# cansat.net
KiCad netlist of a schematic drawn in EAGLE
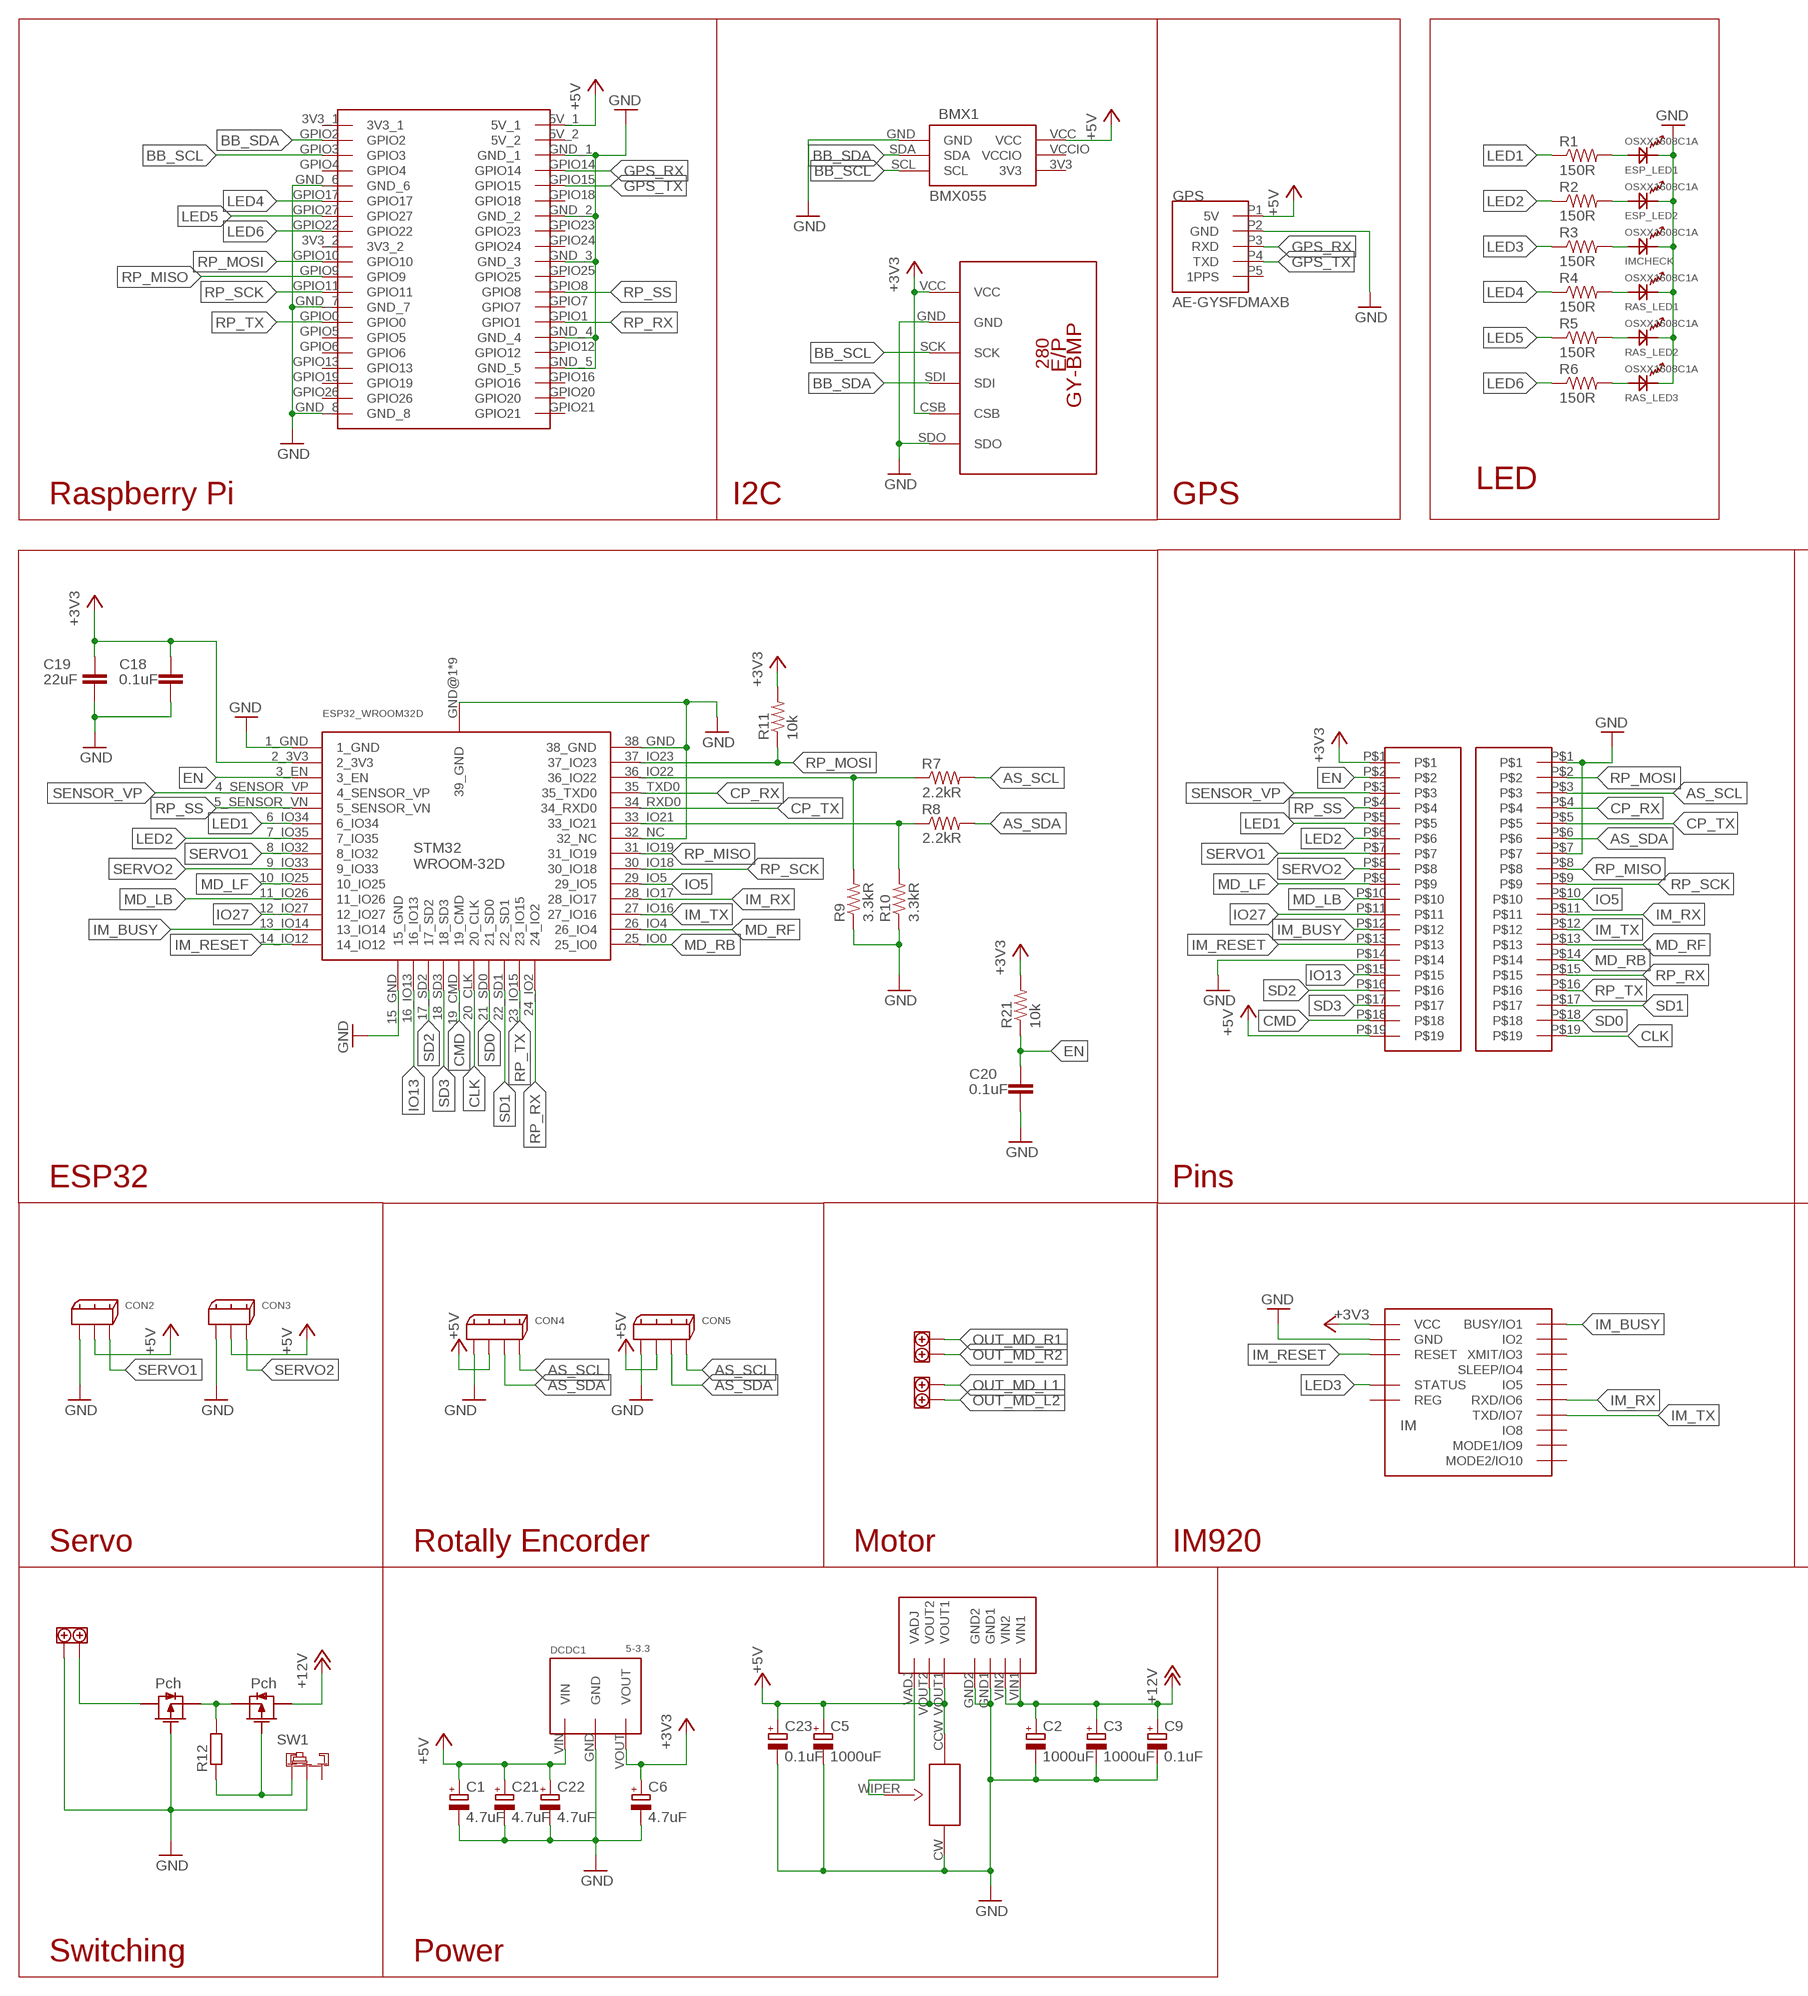
[diagram p0: schematic, sheet 1, part 1 of 2]
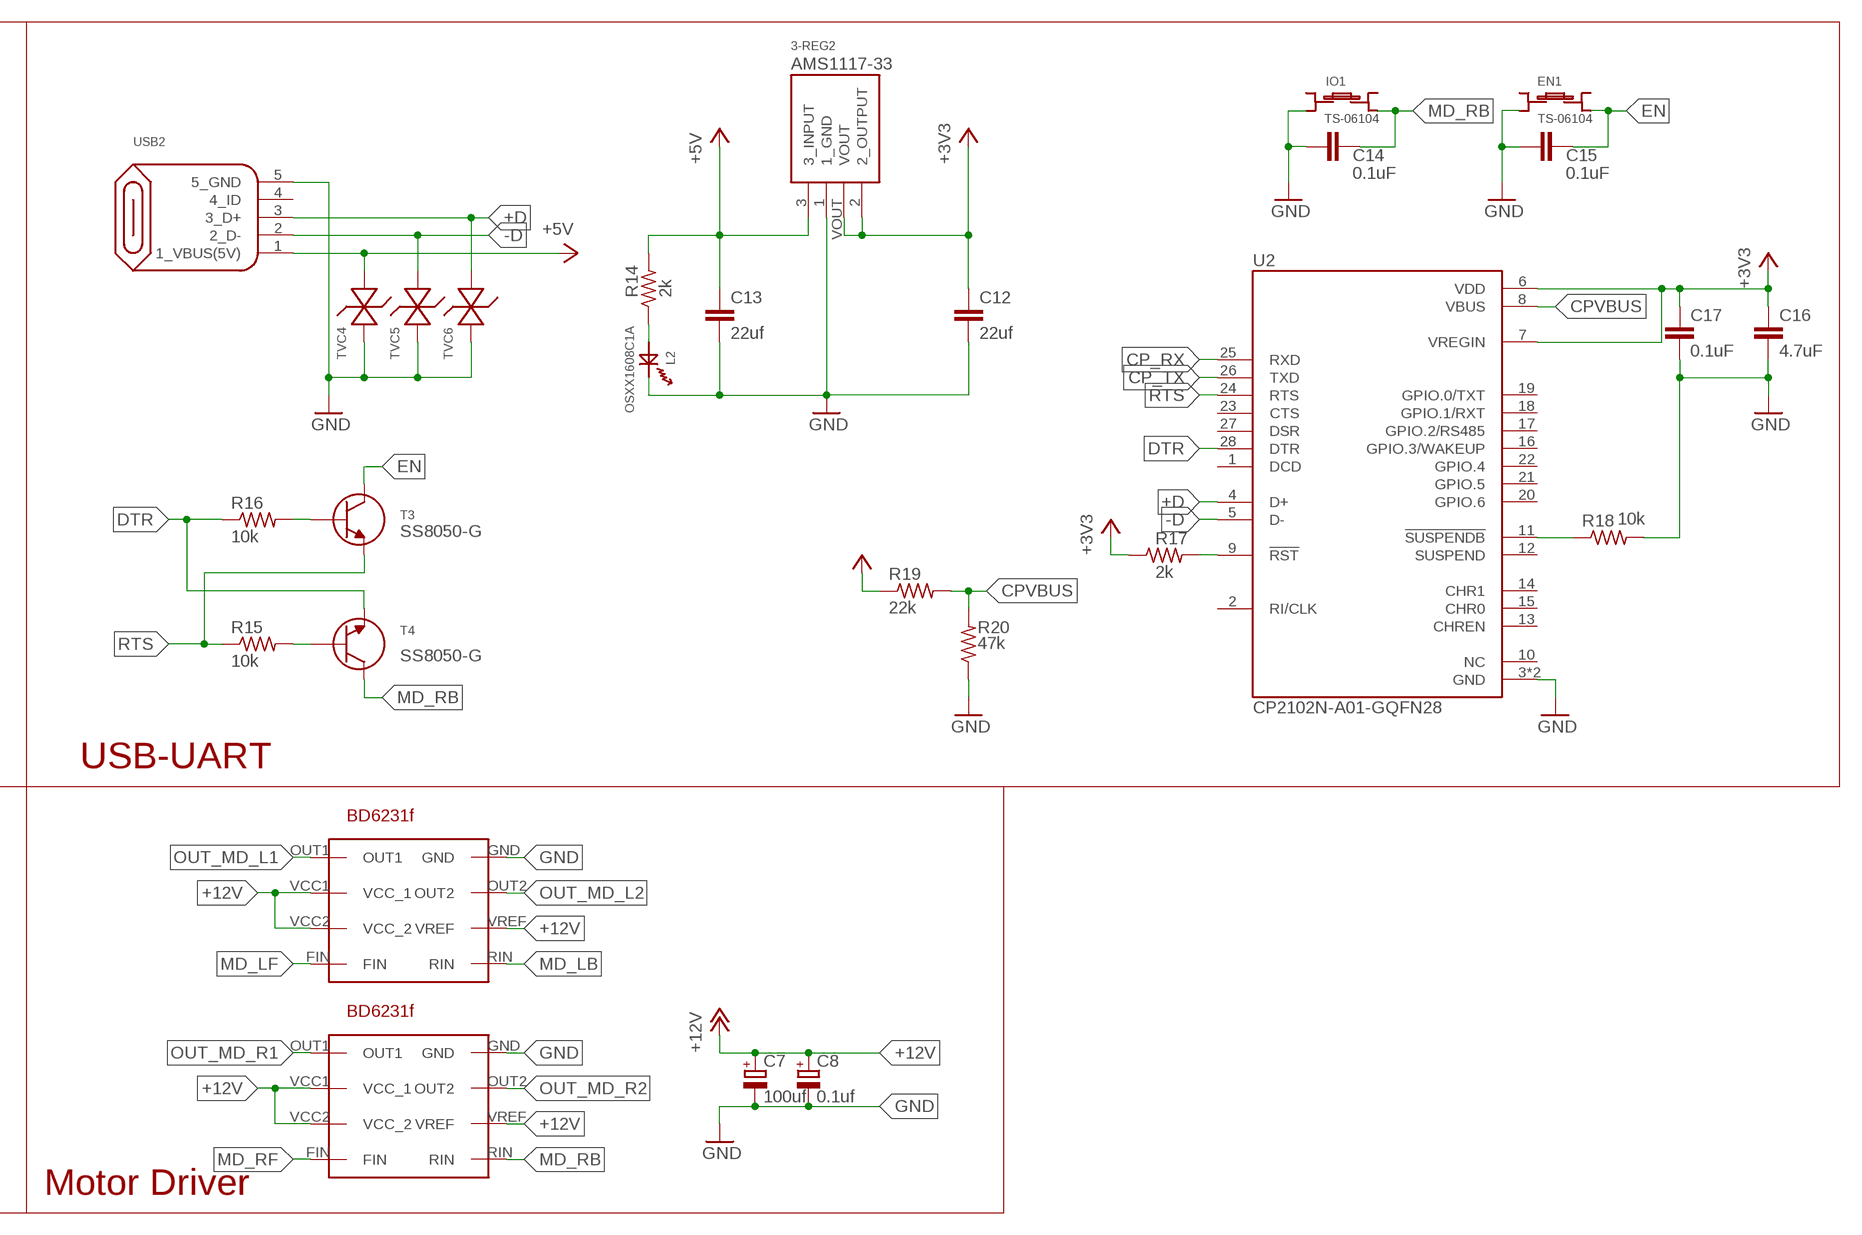
[diagram p1: schematic, sheet 1, part 2 of 2]

(export (version "E")
  (design (tool "Eeschema 10.0.6"))
  (components
    (comp (ref "3-REG2")
      (value "AZ1117CH-3.3TRG1")
      (footprint "eagle-import:AZ1117CH-3.3TRG1")
      (libsource (lib "eagle-import") (part "AZ1117CH-3.3TRG1"))
    )
    (comp (ref "100KR1")
      (value "100kR")
      (footprint "eagle-import:3362P")
      (libsource (lib "eagle-import") (part "3362P"))
    )
    (comp (ref "BMX1")
      (value "BMX055")
      (footprint "eagle-import:BMX055")
      (libsource (lib "eagle-import") (part "BMX055"))
    )
    (comp (ref "C1")
      (value "4.7uF")
      (footprint "eagle-import:E2,5-7")
      (libsource (lib "eagle-import") (part "CPOL-EUE2.5-7"))
    )
    (comp (ref "C2")
      (value "1000uF")
      (footprint "eagle-import:E5-10,5")
      (libsource (lib "eagle-import") (part "CPOL-EUE5-10.5"))
    )
    (comp (ref "C3")
      (value "1000uF")
      (footprint "eagle-import:E5-10,5")
      (libsource (lib "eagle-import") (part "CPOL-EUE5-10.5"))
    )
    (comp (ref "C5")
      (value "1000uF")
      (footprint "eagle-import:E5-10,5")
      (libsource (lib "eagle-import") (part "CPOL-EUE5-10.5"))
    )
    (comp (ref "C6")
      (value "4.7uF")
      (footprint "eagle-import:E2,5-7")
      (libsource (lib "eagle-import") (part "CPOL-EUE2.5-7"))
    )
    (comp (ref "C7")
      (value "100uf")
      (footprint "eagle-import:E2,5-7")
      (libsource (lib "eagle-import") (part "CPOL-EUE2.5-7"))
    )
    (comp (ref "C8")
      (value "0.1uf")
      (footprint "eagle-import:E2,5-7")
      (libsource (lib "eagle-import") (part "CPOL-EUE2.5-7"))
    )
    (comp (ref "C9")
      (value "0.1uF")
      (footprint "eagle-import:E2,5-7")
      (libsource (lib "eagle-import") (part "CPOL-EUE2.5-7"))
    )
    (comp (ref "C12")
      (value "22uf")
      (footprint "eagle-import:C0603")
      (libsource (lib "eagle-import") (part "C-EUC0603"))
    )
    (comp (ref "C13")
      (value "22uf")
      (footprint "eagle-import:C0603")
      (libsource (lib "eagle-import") (part "C-EUC0603"))
    )
    (comp (ref "C14")
      (value "0.1uF")
      (footprint "eagle-import:C0603")
      (libsource (lib "eagle-import") (part "C-EUC0603"))
    )
    (comp (ref "C15")
      (value "0.1uF")
      (footprint "eagle-import:C0603")
      (libsource (lib "eagle-import") (part "C-EUC0603"))
    )
    (comp (ref "C16")
      (value "4.7uF")
      (footprint "eagle-import:C0402")
      (libsource (lib "eagle-import") (part "C-EUC0402"))
    )
    (comp (ref "C17")
      (value "0.1uF")
      (footprint "eagle-import:C0603")
      (libsource (lib "eagle-import") (part "C-EUC0603"))
    )
    (comp (ref "C18")
      (value "0.1uF")
      (footprint "eagle-import:C0603")
      (libsource (lib "eagle-import") (part "C-EUC0603"))
    )
    (comp (ref "C19")
      (value "22uF")
      (footprint "eagle-import:C0603")
      (libsource (lib "eagle-import") (part "C-EUC0603"))
    )
    (comp (ref "C20")
      (value "0.1uF")
      (footprint "eagle-import:C0603")
      (libsource (lib "eagle-import") (part "C-EUC0603"))
    )
    (comp (ref "C21")
      (value "4.7uF")
      (footprint "eagle-import:E2,5-7")
      (libsource (lib "eagle-import") (part "CPOL-EUE2.5-7"))
    )
    (comp (ref "C22")
      (value "4.7uF")
      (footprint "eagle-import:E2,5-7")
      (libsource (lib "eagle-import") (part "CPOL-EUE2.5-7"))
    )
    (comp (ref "C23")
      (value "0.1uF")
      (footprint "eagle-import:E5-10,5")
      (libsource (lib "eagle-import") (part "CPOL-EUE5-10.5"))
    )
    (comp (ref "CON2")
      (value "2.5_MINI-SPOX_3PIN")
      (footprint "eagle-import:2.5_MINI-SPOX_3PIN")
      (libsource (lib "eagle-import") (part "2.5_MINI-SPOX_3PIN"))
    )
    (comp (ref "CON3")
      (value "2.5_MINI-SPOX_3PIN")
      (footprint "eagle-import:2.5_MINI-SPOX_3PIN")
      (libsource (lib "eagle-import") (part "2.5_MINI-SPOX_3PIN"))
    )
    (comp (ref "CON4")
      (value "2.5_MINI-SPOX_4PIN")
      (footprint "eagle-import:2.5_MINI-SPOX_4PIN")
      (libsource (lib "eagle-import") (part "2.5_MINI-SPOX_4PIN"))
    )
    (comp (ref "CON5")
      (value "2.5_MINI-SPOX_4PIN")
      (footprint "eagle-import:2.5_MINI-SPOX_4PIN")
      (libsource (lib "eagle-import") (part "2.5_MINI-SPOX_4PIN"))
    )
    (comp (ref "DCDC1")
      (value "5-3.3")
      (footprint "eagle-import:3.3V0.5A_M78AR05-0.5")
      (libsource (lib "eagle-import") (part "3.3V0.5A_M78AR05-0.5"))
    )
    (comp (ref "EN1")
      (value "TS-06104")
      (footprint "eagle-import:TS-06104")
      (libsource (lib "eagle-import") (part "TS-06104"))
    )
    (comp (ref "ESP32_WROOM32D")
      (value "ESP32-WROOM-32D")
      (footprint "eagle-import:ESP32-WROOM-32D")
      (libsource (lib "eagle-import") (part "ESP32-WROOM-32D"))
    )
    (comp (ref "ESP_LED1")
      (value "OSXX1608C1A")
      (footprint "eagle-import:OSXX1608C1A")
      (libsource (lib "eagle-import") (part "OSXX1608C1A"))
    )
    (comp (ref "ESP_LED2")
      (value "OSXX1608C1A")
      (footprint "eagle-import:OSXX1608C1A")
      (libsource (lib "eagle-import") (part "OSXX1608C1A"))
    )
    (comp (ref "GPS")
      (value "AE-GYSFDMAXB")
      (footprint "eagle-import:AE-GYSFDMAXB")
      (libsource (lib "eagle-import") (part "AE-GYSFDMAXB"))
    )
    (comp (ref "IM")
      (value "IM920C")
      (footprint "eagle-import:IM920C")
      (libsource (lib "eagle-import") (part "IM920C"))
    )
    (comp (ref "IMCHECK")
      (value "OSXX1608C1A")
      (footprint "eagle-import:OSXX1608C1A")
      (libsource (lib "eagle-import") (part "OSXX1608C1A"))
    )
    (comp (ref "IO1")
      (value "TS-06104")
      (footprint "eagle-import:TS-06104")
      (libsource (lib "eagle-import") (part "TS-06104"))
    )
    (comp (ref "L2")
      (value "OSXX1608C1A")
      (footprint "eagle-import:OSXX1608C1A")
      (libsource (lib "eagle-import") (part "OSXX1608C1A"))
    )
    (comp (ref "MD_L")
      (value "BD6231F")
      (footprint "eagle-import:BD6231F")
      (libsource (lib "eagle-import") (part "BD6231F"))
    )
    (comp (ref "MD_R")
      (value "BD6231F")
      (footprint "eagle-import:BD6231F")
      (libsource (lib "eagle-import") (part "BD6231F"))
    )
    (comp (ref "PIN_L")
      (value "19_2.54")
      (footprint "eagle-import:19_2.54")
      (libsource (lib "eagle-import") (part "19_2.54"))
    )
    (comp (ref "PIN_R")
      (value "19_2.54")
      (footprint "eagle-import:19_2.54")
      (libsource (lib "eagle-import") (part "19_2.54"))
    )
    (comp (ref "R1")
      (value "150R")
      (footprint "eagle-import:R0603")
      (libsource (lib "eagle-import") (part "R-US_R0603"))
    )
    (comp (ref "R2")
      (value "150R")
      (footprint "eagle-import:R0603")
      (libsource (lib "eagle-import") (part "R-US_R0603"))
    )
    (comp (ref "R3")
      (value "150R")
      (footprint "eagle-import:R0603")
      (libsource (lib "eagle-import") (part "R-US_R0603"))
    )
    (comp (ref "R4")
      (value "150R")
      (footprint "eagle-import:R0603")
      (libsource (lib "eagle-import") (part "R-US_R0603"))
    )
    (comp (ref "R5")
      (value "150R")
      (footprint "eagle-import:R0603")
      (libsource (lib "eagle-import") (part "R-US_R0603"))
    )
    (comp (ref "R6")
      (value "150R")
      (footprint "eagle-import:R0603")
      (libsource (lib "eagle-import") (part "R-US_R0603"))
    )
    (comp (ref "R7")
      (value "2.2kR")
      (footprint "eagle-import:R0603")
      (libsource (lib "eagle-import") (part "R-US_R0603"))
    )
    (comp (ref "R8")
      (value "2.2kR")
      (footprint "eagle-import:R0603")
      (libsource (lib "eagle-import") (part "R-US_R0603"))
    )
    (comp (ref "R9")
      (value "3.3kR")
      (footprint "eagle-import:R0603")
      (libsource (lib "eagle-import") (part "R-US_R0603"))
    )
    (comp (ref "R10")
      (value "3.3kR")
      (footprint "eagle-import:R0603")
      (libsource (lib "eagle-import") (part "R-US_R0603"))
    )
    (comp (ref "R11")
      (value "10k")
      (footprint "eagle-import:R0201")
      (libsource (lib "eagle-import") (part "R-US_R0201"))
    )
    (comp (ref "R12")
      (value "R-EU_0207/10")
      (footprint "eagle-import:0207_10")
      (libsource (lib "eagle-import") (part "R-EU_0207/10"))
    )
    (comp (ref "R14")
      (value "2k")
      (footprint "eagle-import:R0201")
      (libsource (lib "eagle-import") (part "R-US_R0201"))
    )
    (comp (ref "R15")
      (value "10k")
      (footprint "eagle-import:R0201")
      (libsource (lib "eagle-import") (part "R-US_R0201"))
    )
    (comp (ref "R16")
      (value "10k")
      (footprint "eagle-import:R0201")
      (libsource (lib "eagle-import") (part "R-US_R0201"))
    )
    (comp (ref "R17")
      (value "2k")
      (footprint "eagle-import:R0201")
      (libsource (lib "eagle-import") (part "R-US_R0201"))
    )
    (comp (ref "R18")
      (value "10k")
      (footprint "eagle-import:R0201")
      (libsource (lib "eagle-import") (part "R-US_R0201"))
    )
    (comp (ref "R19")
      (value "22k")
      (footprint "eagle-import:R0201")
      (libsource (lib "eagle-import") (part "R-US_R0201"))
    )
    (comp (ref "R20")
      (value "47k")
      (footprint "eagle-import:R0201")
      (libsource (lib "eagle-import") (part "R-US_R0201"))
    )
    (comp (ref "R21")
      (value "10k")
      (footprint "eagle-import:R0201")
      (libsource (lib "eagle-import") (part "R-US_R0201"))
    )
    (comp (ref "RASPBERRYPI_4B")
      (value "RASPBERRYPI4B")
      (footprint "eagle-import:RASPBERRYPI4B")
      (libsource (lib "eagle-import") (part "RASPBERRYPI4B"))
    )
    (comp (ref "RAS_LED1")
      (value "OSXX1608C1A")
      (footprint "eagle-import:OSXX1608C1A")
      (libsource (lib "eagle-import") (part "OSXX1608C1A"))
    )
    (comp (ref "RAS_LED2")
      (value "OSXX1608C1A")
      (footprint "eagle-import:OSXX1608C1A")
      (libsource (lib "eagle-import") (part "OSXX1608C1A"))
    )
    (comp (ref "RAS_LED3")
      (value "OSXX1608C1A")
      (footprint "eagle-import:OSXX1608C1A")
      (libsource (lib "eagle-import") (part "OSXX1608C1A"))
    )
    (comp (ref "SW1")
      (value "SRIDE_SWITCH")
      (footprint "eagle-import:SRIDE_SWITCH")
      (libsource (lib "eagle-import") (part "SRIDE_SWITCH"))
    )
    (comp (ref "T3")
      (value "NPN_SS8050-G")
      (footprint "eagle-import:NPN_SS8050-G")
      (libsource (lib "eagle-import") (part "NPN_SS8050-G"))
    )
    (comp (ref "T4")
      (value "NPN_SS8050-G")
      (footprint "eagle-import:NPN_SS8050-G")
      (libsource (lib "eagle-import") (part "NPN_SS8050-G"))
    )
    (comp (ref "TM1")
      (value "TERMINAL_SLOPED_2PIN")
      (footprint "eagle-import:TERMINAL_SLOPED_2PIN")
      (libsource (lib "eagle-import") (part "TERMINAL_SLOPED_2PIN"))
    )
    (comp (ref "TM2")
      (value "TERMINAL_SLOPED_2PIN")
      (footprint "eagle-import:TERMINAL_SLOPED_2PIN")
      (libsource (lib "eagle-import") (part "TERMINAL_SLOPED_2PIN"))
    )
    (comp (ref "TM3")
      (value "TERMINAL_SLOPED_2PIN")
      (footprint "eagle-import:TERMINAL_SLOPED_2PIN")
      (libsource (lib "eagle-import") (part "TERMINAL_SLOPED_2PIN"))
    )
    (comp (ref "TVC4")
      (value "ESD5484FCT5G")
      (footprint "eagle-import:ESD5484FCT5G")
      (libsource (lib "eagle-import") (part "ESD5484FCT5G"))
    )
    (comp (ref "TVC5")
      (value "ESD5484FCT5G")
      (footprint "eagle-import:ESD5484FCT5G")
      (libsource (lib "eagle-import") (part "ESD5484FCT5G"))
    )
    (comp (ref "TVC6")
      (value "ESD5484FCT5G")
      (footprint "eagle-import:ESD5484FCT5G")
      (libsource (lib "eagle-import") (part "ESD5484FCT5G"))
    )
    (comp (ref "U$7")
      (value "2SJ681-PCH")
      (footprint "eagle-import:2SJ681")
      (libsource (lib "eagle-import") (part "2SJ681-PCH"))
    )
    (comp (ref "U$8")
      (value "5V3A_KIC-053")
      (footprint "eagle-import:5V3A_KIC-053")
      (libsource (lib "eagle-import") (part "5V3A_KIC-053"))
    )
    (comp (ref "U$9")
      (value "GY-BPM280")
      (footprint "eagle-import:GY-BMP280-FOOTPRINT")
      (libsource (lib "eagle-import") (part "GY-BPM280"))
    )
    (comp (ref "U$10")
      (value "2SJ681-PCH")
      (footprint "eagle-import:2SJ681")
      (libsource (lib "eagle-import") (part "2SJ681-PCH"))
    )
    (comp (ref "U2")
      (value "CP2102N-A01-GQFN28")
      (footprint "eagle-import:QFN50P500X500X80-29N")
      (fields (field (name "MF") "Silicon Labs"))
      (libsource (lib "eagle-import") (part "CP2102N-A01-GQFN28"))
    )
    (comp (ref "USB2")
      (value "MICRO-B_ZX62R-B-5P")
      (footprint "eagle-import:MICRO-B_ZX62R-B-5P")
      (libsource (lib "eagle-import") (part "MICRO-B_ZX62R-B-5P"))
    )
  )
  (nets
    (net (code "1") (name "+3V3") (class "Default")
      (node (ref "3-REG2") (pin "2") (pinfunction "2_OUTPUT_2") (pintype "bidirectional"))
      (node (ref "3-REG2") (pin "VOUT") (pinfunction "VOUT_VOUT") (pintype "bidirectional"))
      (node (ref "C12") (pin "1") (pinfunction "1_1") (pintype "passive"))
      (node (ref "C16") (pin "1") (pinfunction "1_1") (pintype "passive"))
      (node (ref "C17") (pin "1") (pinfunction "1_1") (pintype "passive"))
      (node (ref "C18") (pin "1") (pinfunction "1_1") (pintype "passive"))
      (node (ref "C19") (pin "1") (pinfunction "1_1") (pintype "passive"))
      (node (ref "C6") (pin "+") (pinfunction "+_+") (pintype "passive"))
      (node (ref "DCDC1") (pin "VOUT") (pinfunction "VOUT_VOUT") (pintype "bidirectional"))
      (node (ref "ESP32_WROOM32D") (pin "2_3V3") (pinfunction "2_3V3_2_3V3") (pintype "bidirectional"))
      (node (ref "IM") (pin "$P17") (pinfunction "VCC_$P17") (pintype "bidirectional"))
      (node (ref "PIN_L") (pin "P$1") (pinfunction "P$1_P$1") (pintype "bidirectional"))
      (node (ref "R11") (pin "2") (pinfunction "2_2") (pintype "passive"))
      (node (ref "R17") (pin "1") (pinfunction "1_1") (pintype "passive"))
      (node (ref "R21") (pin "2") (pinfunction "2_2") (pintype "passive"))
      (node (ref "U$9") (pin "CSB") (pinfunction "CSB_CSB") (pintype "bidirectional"))
      (node (ref "U$9") (pin "VCC") (pinfunction "VCC_VCC") (pintype "bidirectional"))
      (node (ref "U2") (pin "6") (pinfunction "VDD_6") (pintype "power_in"))
      (node (ref "U2") (pin "7") (pinfunction "VREGIN_7") (pintype "power_in"))
    )
    (net (code "2") (name "+5V") (class "Default")
      (node (ref "100KR1") (pin "CCW") (pinfunction "CCW_CCW") (pintype "bidirectional"))
      (node (ref "3-REG2") (pin "3") (pinfunction "3_INPUT_3") (pintype "bidirectional"))
      (node (ref "BMX1") (pin "VCC") (pinfunction "VCC_VCC") (pintype "power_in"))
      (node (ref "C1") (pin "+") (pinfunction "+_+") (pintype "passive"))
      (node (ref "C13") (pin "1") (pinfunction "1_1") (pintype "passive"))
      (node (ref "C21") (pin "+") (pinfunction "+_+") (pintype "passive"))
      (node (ref "C22") (pin "+") (pinfunction "+_+") (pintype "passive"))
      (node (ref "C23") (pin "+") (pinfunction "+_+") (pintype "passive"))
      (node (ref "C5") (pin "+") (pinfunction "+_+") (pintype "passive"))
      (node (ref "CON2") (pin "2") (pinfunction "2_2") (pintype "bidirectional"))
      (node (ref "CON3") (pin "2") (pinfunction "2_2") (pintype "bidirectional"))
      (node (ref "CON4") (pin "P$2") (pinfunction "2_P$2") (pintype "bidirectional"))
      (node (ref "CON5") (pin "P$2") (pinfunction "2_P$2") (pintype "bidirectional"))
      (node (ref "DCDC1") (pin "VIN") (pinfunction "VIN_VIN") (pintype "bidirectional"))
      (node (ref "GPS") (pin "P1") (pinfunction "5V_P1") (pintype "bidirectional"))
      (node (ref "PIN_L") (pin "P$19") (pinfunction "P$19_P$19") (pintype "bidirectional"))
      (node (ref "R14") (pin "2") (pinfunction "2_2") (pintype "passive"))
      (node (ref "R19") (pin "1") (pinfunction "1_1") (pintype "passive"))
      (node (ref "RASPBERRYPI_4B") (pin "5V_1") (pinfunction "5V_1_5V_1") (pintype "bidirectional"))
      (node (ref "TVC4") (pin "2_AN") (pinfunction "2_AN_2_AN") (pintype "bidirectional"))
      (node (ref "U$8") (pin "VOUT1") (pinfunction "VOUT1_VOUT1") (pintype "bidirectional"))
      (node (ref "U$8") (pin "VOUT2") (pinfunction "VOUT2_VOUT2") (pintype "bidirectional"))
      (node (ref "USB2") (pin "1") (pinfunction "1_VBUS(5V)_1") (pintype "bidirectional"))
    )
    (net (code "3") (name "+12V") (class "Default")
      (node (ref "C2") (pin "+") (pinfunction "+_+") (pintype "passive"))
      (node (ref "C3") (pin "+") (pinfunction "+_+") (pintype "passive"))
      (node (ref "C7") (pin "+") (pinfunction "+_+") (pintype "passive"))
      (node (ref "C8") (pin "+") (pinfunction "+_+") (pintype "passive"))
      (node (ref "C9") (pin "+") (pinfunction "+_+") (pintype "passive"))
      (node (ref "MD_L") (pin "VCC1") (pinfunction "VCC_1_VCC1") (pintype "bidirectional"))
      (node (ref "MD_L") (pin "VCC2") (pinfunction "VCC_2_VCC2") (pintype "bidirectional"))
      (node (ref "MD_L") (pin "VREF") (pinfunction "VREF_VREF") (pintype "bidirectional"))
      (node (ref "MD_R") (pin "VCC1") (pinfunction "VCC_1_VCC1") (pintype "bidirectional"))
      (node (ref "MD_R") (pin "VCC2") (pinfunction "VCC_2_VCC2") (pintype "bidirectional"))
      (node (ref "MD_R") (pin "VREF") (pinfunction "VREF_VREF") (pintype "bidirectional"))
      (node (ref "U$10") (pin "DRAIN") (pinfunction "DRAIN_DRAIN") (pintype "bidirectional"))
      (node (ref "U$8") (pin "VIN1") (pinfunction "VIN1_VIN1") (pintype "bidirectional"))
      (node (ref "U$8") (pin "VIN2") (pinfunction "VIN2_VIN2") (pintype "bidirectional"))
    )
    (net (code "4") (name "+D") (class "Default")
      (node (ref "TVC6") (pin "2_AN") (pinfunction "2_AN_2_AN") (pintype "bidirectional"))
      (node (ref "U2") (pin "4") (pinfunction "D+_4") (pintype "bidirectional"))
      (node (ref "USB2") (pin "3") (pinfunction "3_D+_3") (pintype "bidirectional"))
    )
    (net (code "5") (name "-D") (class "Default")
      (node (ref "TVC5") (pin "2_AN") (pinfunction "2_AN_2_AN") (pintype "bidirectional"))
      (node (ref "U2") (pin "5") (pinfunction "D-_5") (pintype "bidirectional"))
      (node (ref "USB2") (pin "2") (pinfunction "2_D-_2") (pintype "bidirectional"))
    )
    (net (code "6") (name "/3V3") (class "Default")
      (node (ref "BMX1") (pin "3V3") (pinfunction "3V3_3V3") (pintype "power_in"))
    )
    (net (code "7") (name "/VCCIO") (class "Default")
      (node (ref "BMX1") (pin "VCCIO") (pinfunction "VCCIO_VCCIO") (pintype "power_in"))
    )
    (net (code "8") (name "AS_SCL") (class "Default")
      (node (ref "CON4") (pin "P$4") (pinfunction "4_P$4") (pintype "bidirectional"))
      (node (ref "CON5") (pin "P$4") (pinfunction "4_P$4") (pintype "bidirectional"))
      (node (ref "PIN_R") (pin "P$3") (pinfunction "P$3_P$3") (pintype "bidirectional"))
      (node (ref "R7") (pin "2") (pinfunction "2_2") (pintype "passive"))
    )
    (net (code "9") (name "AS_SDA") (class "Default")
      (node (ref "CON4") (pin "P$3") (pinfunction "3_P$3") (pintype "bidirectional"))
      (node (ref "CON5") (pin "P$3") (pinfunction "3_P$3") (pintype "bidirectional"))
      (node (ref "PIN_R") (pin "P$6") (pinfunction "P$6_P$6") (pintype "bidirectional"))
      (node (ref "R8") (pin "2") (pinfunction "2_2") (pintype "passive"))
    )
    (net (code "10") (name "BB_SCL") (class "Default")
      (node (ref "BMX1") (pin "SCL") (pinfunction "SCL_SCL") (pintype "bidirectional"))
      (node (ref "RASPBERRYPI_4B") (pin "GPIO3") (pinfunction "GPIO3_GPIO3") (pintype "bidirectional"))
      (node (ref "U$9") (pin "SCK") (pinfunction "SCK_SCK") (pintype "bidirectional"))
    )
    (net (code "11") (name "BB_SDA") (class "Default")
      (node (ref "BMX1") (pin "SDA") (pinfunction "SDA_SDA") (pintype "bidirectional"))
      (node (ref "RASPBERRYPI_4B") (pin "GPIO2") (pinfunction "GPIO2_GPIO2") (pintype "bidirectional"))
      (node (ref "U$9") (pin "SDI") (pinfunction "SDI_SDI") (pintype "bidirectional"))
    )
    (net (code "12") (name "CLK") (class "Default")
      (node (ref "ESP32_WROOM32D") (pin "20_CLK") (pinfunction "20_CLK_20_CLK") (pintype "bidirectional"))
      (node (ref "PIN_R") (pin "P$19") (pinfunction "P$19_P$19") (pintype "bidirectional"))
    )
    (net (code "13") (name "CMD") (class "Default")
      (node (ref "ESP32_WROOM32D") (pin "19_CMD") (pinfunction "19_CMD_19_CMD") (pintype "bidirectional"))
      (node (ref "PIN_L") (pin "P$18") (pinfunction "P$18_P$18") (pintype "bidirectional"))
    )
    (net (code "14") (name "CPVBUS") (class "Default")
      (node (ref "R19") (pin "2") (pinfunction "2_2") (pintype "passive"))
      (node (ref "R20") (pin "2") (pinfunction "2_2") (pintype "passive"))
      (node (ref "U2") (pin "8") (pinfunction "VBUS_8") (pintype "power_in"))
    )
    (net (code "15") (name "CP_RX") (class "Default")
      (node (ref "ESP32_WROOM32D") (pin "35_TXD0") (pinfunction "35_TXD0_35_TXD0") (pintype "bidirectional"))
      (node (ref "PIN_R") (pin "P$4") (pinfunction "P$4_P$4") (pintype "bidirectional"))
      (node (ref "U2") (pin "25") (pinfunction "RXD_25") (pintype "input"))
    )
    (net (code "16") (name "CP_TX") (class "Default")
      (node (ref "ESP32_WROOM32D") (pin "34_RXD0") (pinfunction "34_RXD0_34_RXD0") (pintype "bidirectional"))
      (node (ref "PIN_R") (pin "P$5") (pinfunction "P$5_P$5") (pintype "bidirectional"))
      (node (ref "U2") (pin "26") (pinfunction "TXD_26") (pintype "output"))
    )
    (net (code "17") (name "DTR") (class "Default")
      (node (ref "R16") (pin "1") (pinfunction "1_1") (pintype "passive"))
      (node (ref "T4") (pin "2") (pinfunction "2_2") (pintype "bidirectional"))
      (node (ref "U2") (pin "28") (pinfunction "DTR_28") (pintype "output"))
    )
    (net (code "18") (name "EN") (class "Default")
      (node (ref "C15") (pin "1") (pinfunction "1_1") (pintype "passive"))
      (node (ref "C20") (pin "1") (pinfunction "1_1") (pintype "passive"))
      (node (ref "EN1") (pin "D") (pinfunction "D_D") (pintype "bidirectional"))
      (node (ref "ESP32_WROOM32D") (pin "3_EN") (pinfunction "3_EN_3_EN") (pintype "bidirectional"))
      (node (ref "PIN_L") (pin "P$2") (pinfunction "P$2_P$2") (pintype "bidirectional"))
      (node (ref "R21") (pin "1") (pinfunction "1_1") (pintype "passive"))
      (node (ref "T3") (pin "3") (pinfunction "3_3") (pintype "bidirectional"))
    )
    (net (code "19") (name "GND") (class "Default")
      (node (ref "100KR1") (pin "CW") (pinfunction "CW_CW") (pintype "bidirectional"))
      (node (ref "3-REG2") (pin "1") (pinfunction "1_GND_1") (pintype "bidirectional"))
      (node (ref "BMX1") (pin "GND") (pinfunction "GND_GND") (pintype "power_in"))
      (node (ref "C1") (pin "-") (pinfunction "-_-") (pintype "passive"))
      (node (ref "C12") (pin "2") (pinfunction "2_2") (pintype "passive"))
      (node (ref "C13") (pin "2") (pinfunction "2_2") (pintype "passive"))
      (node (ref "C14") (pin "2") (pinfunction "2_2") (pintype "passive"))
      (node (ref "C15") (pin "2") (pinfunction "2_2") (pintype "passive"))
      (node (ref "C16") (pin "2") (pinfunction "2_2") (pintype "passive"))
      (node (ref "C17") (pin "2") (pinfunction "2_2") (pintype "passive"))
      (node (ref "C18") (pin "2") (pinfunction "2_2") (pintype "passive"))
      (node (ref "C19") (pin "2") (pinfunction "2_2") (pintype "passive"))
      (node (ref "C2") (pin "-") (pinfunction "-_-") (pintype "passive"))
      (node (ref "C20") (pin "2") (pinfunction "2_2") (pintype "passive"))
      (node (ref "C21") (pin "-") (pinfunction "-_-") (pintype "passive"))
      (node (ref "C22") (pin "-") (pinfunction "-_-") (pintype "passive"))
      (node (ref "C23") (pin "-") (pinfunction "-_-") (pintype "passive"))
      (node (ref "C3") (pin "-") (pinfunction "-_-") (pintype "passive"))
      (node (ref "C5") (pin "-") (pinfunction "-_-") (pintype "passive"))
      (node (ref "C6") (pin "-") (pinfunction "-_-") (pintype "passive"))
      (node (ref "C7") (pin "-") (pinfunction "-_-") (pintype "passive"))
      (node (ref "C8") (pin "-") (pinfunction "-_-") (pintype "passive"))
      (node (ref "C9") (pin "-") (pinfunction "-_-") (pintype "passive"))
      (node (ref "CON2") (pin "1") (pinfunction "1_1") (pintype "bidirectional"))
      (node (ref "CON3") (pin "1") (pinfunction "1_1") (pintype "bidirectional"))
      (node (ref "CON4") (pin "P$1") (pinfunction "1_P$1") (pintype "bidirectional"))
      (node (ref "CON5") (pin "P$1") (pinfunction "1_P$1") (pintype "bidirectional"))
      (node (ref "DCDC1") (pin "GND") (pinfunction "GND_GND") (pintype "bidirectional"))
      (node (ref "EN1") (pin "B") (pinfunction "B_B") (pintype "bidirectional"))
      (node (ref "ESP32_WROOM32D") (pin "15_GND") (pinfunction "15_GND_15_GND") (pintype "bidirectional"))
      (node (ref "ESP32_WROOM32D") (pin "1_GND") (pinfunction "1_GND_1_GND") (pintype "bidirectional"))
      (node (ref "ESP32_WROOM32D") (pin "32_NC") (pinfunction "32_NC_32_NC") (pintype "bidirectional"))
      (node (ref "ESP32_WROOM32D") (pin "38_GND") (pinfunction "38_GND_38_GND") (pintype "bidirectional"))
      (node (ref "ESP32_WROOM32D") (pin "GND@1") (pinfunction "39_GND_GND@1") (pintype "bidirectional"))
      (node (ref "ESP32_WROOM32D") (pin "GND@2") (pinfunction "39_GND_GND@2") (pintype "bidirectional"))
      (node (ref "ESP32_WROOM32D") (pin "GND@3") (pinfunction "39_GND_GND@3") (pintype "bidirectional"))
      (node (ref "ESP32_WROOM32D") (pin "GND@4") (pinfunction "39_GND_GND@4") (pintype "bidirectional"))
      (node (ref "ESP32_WROOM32D") (pin "GND@5") (pinfunction "39_GND_GND@5") (pintype "bidirectional"))
      (node (ref "ESP32_WROOM32D") (pin "GND@6") (pinfunction "39_GND_GND@6") (pintype "bidirectional"))
      (node (ref "ESP32_WROOM32D") (pin "GND@7") (pinfunction "39_GND_GND@7") (pintype "bidirectional"))
      (node (ref "ESP32_WROOM32D") (pin "GND@8") (pinfunction "39_GND_GND@8") (pintype "bidirectional"))
      (node (ref "ESP32_WROOM32D") (pin "GND@9") (pinfunction "39_GND_GND@9") (pintype "bidirectional"))
      (node (ref "ESP_LED1") (pin "CT") (pinfunction "CT_CT") (pintype "bidirectional"))
      (node (ref "ESP_LED2") (pin "CT") (pinfunction "CT_CT") (pintype "bidirectional"))
      (node (ref "GPS") (pin "P2") (pinfunction "GND_P2") (pintype "bidirectional"))
      (node (ref "IM") (pin "$P18") (pinfunction "GND_$P18") (pintype "bidirectional"))
      (node (ref "IMCHECK") (pin "CT") (pinfunction "CT_CT") (pintype "bidirectional"))
      (node (ref "IO1") (pin "B") (pinfunction "B_B") (pintype "bidirectional"))
      (node (ref "L2") (pin "CT") (pinfunction "CT_CT") (pintype "bidirectional"))
      (node (ref "MD_L") (pin "GND") (pinfunction "GND_GND") (pintype "bidirectional"))
      (node (ref "MD_R") (pin "GND") (pinfunction "GND_GND") (pintype "bidirectional"))
      (node (ref "PIN_L") (pin "P$14") (pinfunction "P$14_P$14") (pintype "bidirectional"))
      (node (ref "PIN_R") (pin "P$1") (pinfunction "P$1_P$1") (pintype "bidirectional"))
      (node (ref "PIN_R") (pin "P$7") (pinfunction "P$7_P$7") (pintype "bidirectional"))
      (node (ref "R10") (pin "1") (pinfunction "1_1") (pintype "passive"))
      (node (ref "R18") (pin "2") (pinfunction "2_2") (pintype "passive"))
      (node (ref "R20") (pin "1") (pinfunction "1_1") (pintype "passive"))
      (node (ref "R9") (pin "1") (pinfunction "1_1") (pintype "passive"))
      (node (ref "RASPBERRYPI_4B") (pin "GND_1") (pinfunction "GND_1_GND_1") (pintype "bidirectional"))
      (node (ref "RASPBERRYPI_4B") (pin "GND_2") (pinfunction "GND_2_GND_2") (pintype "bidirectional"))
      (node (ref "RASPBERRYPI_4B") (pin "GND_3") (pinfunction "GND_3_GND_3") (pintype "bidirectional"))
      (node (ref "RASPBERRYPI_4B") (pin "GND_4") (pinfunction "GND_4_GND_4") (pintype "bidirectional"))
      (node (ref "RASPBERRYPI_4B") (pin "GND_5") (pinfunction "GND_5_GND_5") (pintype "bidirectional"))
      (node (ref "RASPBERRYPI_4B") (pin "GND_6") (pinfunction "GND_6_GND_6") (pintype "bidirectional"))
      (node (ref "RASPBERRYPI_4B") (pin "GND_7") (pinfunction "GND_7_GND_7") (pintype "bidirectional"))
      (node (ref "RASPBERRYPI_4B") (pin "GND_8") (pinfunction "GND_8_GND_8") (pintype "bidirectional"))
      (node (ref "RAS_LED1") (pin "CT") (pinfunction "CT_CT") (pintype "bidirectional"))
      (node (ref "RAS_LED2") (pin "CT") (pinfunction "CT_CT") (pintype "bidirectional"))
      (node (ref "RAS_LED3") (pin "CT") (pinfunction "CT_CT") (pintype "bidirectional"))
      (node (ref "SW1") (pin "LR") (pinfunction "LR_LR") (pintype "bidirectional"))
      (node (ref "TM3") (pin "2") (pinfunction "2_2") (pintype "bidirectional"))
      (node (ref "TVC4") (pin "1_CT") (pinfunction "1_CT_1_CT") (pintype "bidirectional"))
      (node (ref "TVC5") (pin "1_CT") (pinfunction "1_CT_1_CT") (pintype "bidirectional"))
      (node (ref "TVC6") (pin "1_CT") (pinfunction "1_CT_1_CT") (pintype "bidirectional"))
      (node (ref "U$7") (pin "GATE") (pinfunction "GATE_GATE") (pintype "bidirectional"))
      (node (ref "U$8") (pin "GND1") (pinfunction "GND1_GND1") (pintype "bidirectional"))
      (node (ref "U$8") (pin "GND2") (pinfunction "GND2_GND2") (pintype "bidirectional"))
      (node (ref "U$9") (pin "GND") (pinfunction "GND_GND") (pintype "bidirectional"))
      (node (ref "U$9") (pin "SDO") (pinfunction "SDO_SDO") (pintype "bidirectional"))
      (node (ref "U2") (pin "29") (pinfunction "GND_29") (pintype "power_in"))
      (node (ref "U2") (pin "3") (pinfunction "GND_3") (pintype "power_in"))
      (node (ref "USB2") (pin "5") (pinfunction "5_GND_5") (pintype "bidirectional"))
    )
    (net (code "20") (name "GPS_RX") (class "Default")
      (node (ref "GPS") (pin "P3") (pinfunction "RXD_P3") (pintype "bidirectional"))
      (node (ref "RASPBERRYPI_4B") (pin "GPIO14") (pinfunction "GPIO14_GPIO14") (pintype "bidirectional"))
    )
    (net (code "21") (name "GPS_TX") (class "Default")
      (node (ref "GPS") (pin "P4") (pinfunction "TXD_P4") (pintype "bidirectional"))
      (node (ref "RASPBERRYPI_4B") (pin "GPIO15") (pinfunction "GPIO15_GPIO15") (pintype "bidirectional"))
    )
    (net (code "22") (name "IM_BUSY") (class "Default")
      (node (ref "ESP32_WROOM32D") (pin "13_IO14") (pinfunction "13_IO14_13_IO14") (pintype "bidirectional"))
      (node (ref "IM") (pin "$P1") (pinfunction "BUSY/IO1_$P1") (pintype "bidirectional"))
      (node (ref "PIN_L") (pin "P$12") (pinfunction "P$12_P$12") (pintype "bidirectional"))
    )
    (net (code "23") (name "IM_RESET") (class "Default")
      (node (ref "ESP32_WROOM32D") (pin "14_IO12") (pinfunction "14_IO12_14_IO12") (pintype "bidirectional"))
      (node (ref "IM") (pin "$P19") (pinfunction "RESET_$P19") (pintype "bidirectional"))
      (node (ref "PIN_L") (pin "P$13") (pinfunction "P$13_P$13") (pintype "bidirectional"))
    )
    (net (code "24") (name "IM_RX") (class "Default")
      (node (ref "ESP32_WROOM32D") (pin "28_IO17") (pinfunction "28_IO17_28_IO17") (pintype "bidirectional"))
      (node (ref "IM") (pin "$P6") (pinfunction "RXD/IO6_$P6") (pintype "bidirectional"))
      (node (ref "PIN_R") (pin "P$11") (pinfunction "P$11_P$11") (pintype "bidirectional"))
    )
    (net (code "25") (name "IM_TX") (class "Default")
      (node (ref "ESP32_WROOM32D") (pin "27_IO16") (pinfunction "27_IO16_27_IO16") (pintype "bidirectional"))
      (node (ref "IM") (pin "$P7") (pinfunction "TXD/IO7_$P7") (pintype "bidirectional"))
      (node (ref "PIN_R") (pin "P$12") (pinfunction "P$12_P$12") (pintype "bidirectional"))
    )
    (net (code "26") (name "IO5") (class "Default")
      (node (ref "ESP32_WROOM32D") (pin "29_IO5") (pinfunction "29_IO5_29_IO5") (pintype "bidirectional"))
      (node (ref "PIN_R") (pin "P$10") (pinfunction "P$10_P$10") (pintype "bidirectional"))
    )
    (net (code "27") (name "IO13") (class "Default")
      (node (ref "ESP32_WROOM32D") (pin "16_IO13") (pinfunction "16_IO13_16_IO13") (pintype "bidirectional"))
      (node (ref "PIN_L") (pin "P$15") (pinfunction "P$15_P$15") (pintype "bidirectional"))
    )
    (net (code "28") (name "IO27") (class "Default")
      (node (ref "ESP32_WROOM32D") (pin "12_IO27") (pinfunction "12_IO27_12_IO27") (pintype "bidirectional"))
      (node (ref "PIN_L") (pin "P$11") (pinfunction "P$11_P$11") (pintype "bidirectional"))
    )
    (net (code "29") (name "LED1") (class "Default")
      (node (ref "ESP32_WROOM32D") (pin "6_IO34") (pinfunction "6_IO34_6_IO34") (pintype "bidirectional"))
      (node (ref "PIN_L") (pin "P$5") (pinfunction "P$5_P$5") (pintype "bidirectional"))
      (node (ref "R1") (pin "1") (pinfunction "1_1") (pintype "passive"))
    )
    (net (code "30") (name "LED2") (class "Default")
      (node (ref "ESP32_WROOM32D") (pin "7_IO35") (pinfunction "7_IO35_7_IO35") (pintype "bidirectional"))
      (node (ref "PIN_L") (pin "P$6") (pinfunction "P$6_P$6") (pintype "bidirectional"))
      (node (ref "R2") (pin "1") (pinfunction "1_1") (pintype "passive"))
    )
    (net (code "31") (name "LED3") (class "Default")
      (node (ref "IM") (pin "$P15") (pinfunction "STATUS_$P15") (pintype "bidirectional"))
      (node (ref "R3") (pin "1") (pinfunction "1_1") (pintype "passive"))
    )
    (net (code "32") (name "LED4") (class "Default")
      (node (ref "R4") (pin "1") (pinfunction "1_1") (pintype "passive"))
      (node (ref "RASPBERRYPI_4B") (pin "GPIO17") (pinfunction "GPIO17_GPIO17") (pintype "bidirectional"))
    )
    (net (code "33") (name "LED5") (class "Default")
      (node (ref "R5") (pin "1") (pinfunction "1_1") (pintype "passive"))
      (node (ref "RASPBERRYPI_4B") (pin "GPIO27") (pinfunction "GPIO27_GPIO27") (pintype "bidirectional"))
    )
    (net (code "34") (name "LED6") (class "Default")
      (node (ref "R6") (pin "1") (pinfunction "1_1") (pintype "passive"))
      (node (ref "RASPBERRYPI_4B") (pin "GPIO22") (pinfunction "GPIO22_GPIO22") (pintype "bidirectional"))
    )
    (net (code "35") (name "MD_LB") (class "Default")
      (node (ref "ESP32_WROOM32D") (pin "11_IO26") (pinfunction "11_IO26_11_IO26") (pintype "bidirectional"))
      (node (ref "MD_L") (pin "RIN") (pinfunction "RIN_RIN") (pintype "bidirectional"))
      (node (ref "PIN_L") (pin "P$10") (pinfunction "P$10_P$10") (pintype "bidirectional"))
    )
    (net (code "36") (name "MD_LF") (class "Default")
      (node (ref "ESP32_WROOM32D") (pin "10_IO25") (pinfunction "10_IO25_10_IO25") (pintype "bidirectional"))
      (node (ref "MD_L") (pin "FIN") (pinfunction "FIN_FIN") (pintype "bidirectional"))
      (node (ref "PIN_L") (pin "P$9") (pinfunction "P$9_P$9") (pintype "bidirectional"))
    )
    (net (code "37") (name "MD_RB") (class "Default")
      (node (ref "C14") (pin "1") (pinfunction "1_1") (pintype "passive"))
      (node (ref "ESP32_WROOM32D") (pin "25_IO0") (pinfunction "25_IO0_25_IO0") (pintype "bidirectional"))
      (node (ref "IO1") (pin "D") (pinfunction "D_D") (pintype "bidirectional"))
      (node (ref "MD_R") (pin "RIN") (pinfunction "RIN_RIN") (pintype "bidirectional"))
      (node (ref "PIN_R") (pin "P$14") (pinfunction "P$14_P$14") (pintype "bidirectional"))
      (node (ref "T4") (pin "3") (pinfunction "3_3") (pintype "bidirectional"))
    )
    (net (code "38") (name "MD_RF") (class "Default")
      (node (ref "ESP32_WROOM32D") (pin "26_IO4") (pinfunction "26_IO4_26_IO4") (pintype "bidirectional"))
      (node (ref "MD_R") (pin "FIN") (pinfunction "FIN_FIN") (pintype "bidirectional"))
      (node (ref "PIN_R") (pin "P$13") (pinfunction "P$13_P$13") (pintype "bidirectional"))
    )
    (net (code "39") (name "Net-(100KR1-PadWIPER)") (class "Default")
      (node (ref "100KR1") (pin "WIPER") (pinfunction "WIPER_WIPER") (pintype "bidirectional"))
      (node (ref "U$8") (pin "VADJ") (pinfunction "VADJ_VADJ") (pintype "bidirectional"))
    )
    (net (code "40") (name "Net-(ESP32_WROOM32D-Pad33_IO21)") (class "Default")
      (node (ref "ESP32_WROOM32D") (pin "33_IO21") (pinfunction "33_IO21_33_IO21") (pintype "bidirectional"))
      (node (ref "R10") (pin "2") (pinfunction "2_2") (pintype "passive"))
      (node (ref "R8") (pin "1") (pinfunction "1_1") (pintype "passive"))
    )
    (net (code "41") (name "Net-(ESP32_WROOM32D-Pad36_IO22)") (class "Default")
      (node (ref "ESP32_WROOM32D") (pin "36_IO22") (pinfunction "36_IO22_36_IO22") (pintype "bidirectional"))
      (node (ref "R7") (pin "1") (pinfunction "1_1") (pintype "passive"))
      (node (ref "R9") (pin "2") (pinfunction "2_2") (pintype "passive"))
    )
    (net (code "42") (name "Net-(ESP_LED1-PadAN)") (class "Default")
      (node (ref "ESP_LED1") (pin "AN") (pinfunction "AN_AN") (pintype "bidirectional"))
      (node (ref "R1") (pin "2") (pinfunction "2_2") (pintype "passive"))
    )
    (net (code "43") (name "Net-(ESP_LED2-PadAN)") (class "Default")
      (node (ref "ESP_LED2") (pin "AN") (pinfunction "AN_AN") (pintype "bidirectional"))
      (node (ref "R2") (pin "2") (pinfunction "2_2") (pintype "passive"))
    )
    (net (code "44") (name "Net-(IMCHECK-PadAN)") (class "Default")
      (node (ref "IMCHECK") (pin "AN") (pinfunction "AN_AN") (pintype "bidirectional"))
      (node (ref "R3") (pin "2") (pinfunction "2_2") (pintype "passive"))
    )
    (net (code "45") (name "Net-(L2-PadAN)") (class "Default")
      (node (ref "L2") (pin "AN") (pinfunction "AN_AN") (pintype "bidirectional"))
      (node (ref "R14") (pin "1") (pinfunction "1_1") (pintype "passive"))
    )
    (net (code "46") (name "Net-(R4-Pad2)") (class "Default")
      (node (ref "R4") (pin "2") (pinfunction "2_2") (pintype "passive"))
      (node (ref "RAS_LED1") (pin "AN") (pinfunction "AN_AN") (pintype "bidirectional"))
    )
    (net (code "47") (name "Net-(R5-Pad2)") (class "Default")
      (node (ref "R5") (pin "2") (pinfunction "2_2") (pintype "passive"))
      (node (ref "RAS_LED2") (pin "AN") (pinfunction "AN_AN") (pintype "bidirectional"))
    )
    (net (code "48") (name "Net-(R6-Pad2)") (class "Default")
      (node (ref "R6") (pin "2") (pinfunction "2_2") (pintype "passive"))
      (node (ref "RAS_LED3") (pin "AN") (pinfunction "AN_AN") (pintype "bidirectional"))
    )
    (net (code "49") (name "Net-(R12-Pad1)") (class "Default")
      (node (ref "R12") (pin "1") (pinfunction "1_1") (pintype "passive"))
      (node (ref "SW1") (pin "L") (pinfunction "L_L") (pintype "bidirectional"))
      (node (ref "U$10") (pin "GATE") (pinfunction "GATE_GATE") (pintype "bidirectional"))
    )
    (net (code "50") (name "Net-(R12-Pad2)") (class "Default")
      (node (ref "R12") (pin "2") (pinfunction "2_2") (pintype "passive"))
      (node (ref "U$10") (pin "SOURCE") (pinfunction "SOURCE_SOURCE") (pintype "bidirectional"))
      (node (ref "U$7") (pin "SOURCE") (pinfunction "SOURCE_SOURCE") (pintype "bidirectional"))
    )
    (net (code "51") (name "Net-(R15-Pad2)") (class "Default")
      (node (ref "R15") (pin "2") (pinfunction "2_2") (pintype "passive"))
      (node (ref "T4") (pin "1") (pinfunction "1_1") (pintype "bidirectional"))
    )
    (net (code "52") (name "Net-(R16-Pad2)") (class "Default")
      (node (ref "R16") (pin "2") (pinfunction "2_2") (pintype "passive"))
      (node (ref "T3") (pin "1") (pinfunction "1_1") (pintype "bidirectional"))
    )
    (net (code "53") (name "Net-(TM3-Pad1)") (class "Default")
      (node (ref "TM3") (pin "1") (pinfunction "1_1") (pintype "bidirectional"))
      (node (ref "U$7") (pin "DRAIN") (pinfunction "DRAIN_DRAIN") (pintype "bidirectional"))
    )
    (net (code "54") (name "Net-(U2-~{RST})") (class "Default")
      (node (ref "R17") (pin "2") (pinfunction "2_2") (pintype "passive"))
      (node (ref "U2") (pin "9") (pinfunction "~{RST}_9") (pintype "input"))
    )
    (net (code "55") (name "Net-(U2-~{SUSPENDB})") (class "Default")
      (node (ref "R18") (pin "1") (pinfunction "1_1") (pintype "passive"))
      (node (ref "U2") (pin "11") (pinfunction "~{SUSPENDB}_11") (pintype "output"))
    )
    (net (code "56") (name "OUT_MD_L1") (class "Default")
      (node (ref "MD_L") (pin "OUT1") (pinfunction "OUT1_OUT1") (pintype "bidirectional"))
      (node (ref "TM2") (pin "1") (pinfunction "1_1") (pintype "bidirectional"))
    )
    (net (code "57") (name "OUT_MD_L2") (class "Default")
      (node (ref "MD_L") (pin "OUT2") (pinfunction "OUT2_OUT2") (pintype "bidirectional"))
      (node (ref "TM2") (pin "2") (pinfunction "2_2") (pintype "bidirectional"))
    )
    (net (code "58") (name "OUT_MD_R1") (class "Default")
      (node (ref "MD_R") (pin "OUT1") (pinfunction "OUT1_OUT1") (pintype "bidirectional"))
      (node (ref "TM1") (pin "1") (pinfunction "1_1") (pintype "bidirectional"))
    )
    (net (code "59") (name "OUT_MD_R2") (class "Default")
      (node (ref "MD_R") (pin "OUT2") (pinfunction "OUT2_OUT2") (pintype "bidirectional"))
      (node (ref "TM1") (pin "2") (pinfunction "2_2") (pintype "bidirectional"))
    )
    (net (code "60") (name "RP_MISO") (class "Default")
      (node (ref "ESP32_WROOM32D") (pin "31_IO19") (pinfunction "31_IO19_31_IO19") (pintype "bidirectional"))
      (node (ref "PIN_R") (pin "P$8") (pinfunction "P$8_P$8") (pintype "bidirectional"))
      (node (ref "RASPBERRYPI_4B") (pin "GPIO9") (pinfunction "GPIO9_GPIO9") (pintype "bidirectional"))
    )
    (net (code "61") (name "RP_MOSI") (class "Default")
      (node (ref "ESP32_WROOM32D") (pin "37_IO23") (pinfunction "37_IO23_37_IO23") (pintype "bidirectional"))
      (node (ref "PIN_R") (pin "P$2") (pinfunction "P$2_P$2") (pintype "bidirectional"))
      (node (ref "R11") (pin "1") (pinfunction "1_1") (pintype "passive"))
      (node (ref "RASPBERRYPI_4B") (pin "GPIO10") (pinfunction "GPIO10_GPIO10") (pintype "bidirectional"))
    )
    (net (code "62") (name "RP_RX") (class "Default")
      (node (ref "ESP32_WROOM32D") (pin "24_IO2") (pinfunction "24_IO2_24_IO2") (pintype "bidirectional"))
      (node (ref "PIN_R") (pin "P$15") (pinfunction "P$15_P$15") (pintype "bidirectional"))
      (node (ref "RASPBERRYPI_4B") (pin "GPIO1") (pinfunction "GPIO1_GPIO1") (pintype "bidirectional"))
    )
    (net (code "63") (name "RP_SCK") (class "Default")
      (node (ref "ESP32_WROOM32D") (pin "30_IO18") (pinfunction "30_IO18_30_IO18") (pintype "bidirectional"))
      (node (ref "PIN_R") (pin "P$9") (pinfunction "P$9_P$9") (pintype "bidirectional"))
      (node (ref "RASPBERRYPI_4B") (pin "GPIO11") (pinfunction "GPIO11_GPIO11") (pintype "bidirectional"))
    )
    (net (code "64") (name "RP_SS") (class "Default")
      (node (ref "ESP32_WROOM32D") (pin "5_SENSOR_VN") (pinfunction "5_SENSOR_VN_5_SENSOR_VN") (pintype "bidirectional"))
      (node (ref "PIN_L") (pin "P$4") (pinfunction "P$4_P$4") (pintype "bidirectional"))
      (node (ref "RASPBERRYPI_4B") (pin "GPIO8") (pinfunction "GPIO8_GPIO8") (pintype "bidirectional"))
    )
    (net (code "65") (name "RP_TX") (class "Default")
      (node (ref "ESP32_WROOM32D") (pin "23_IO15") (pinfunction "23_IO15_23_IO15") (pintype "bidirectional"))
      (node (ref "PIN_R") (pin "P$16") (pinfunction "P$16_P$16") (pintype "bidirectional"))
      (node (ref "RASPBERRYPI_4B") (pin "GPIO0") (pinfunction "GPIO0_GPIO0") (pintype "bidirectional"))
    )
    (net (code "66") (name "RTS") (class "Default")
      (node (ref "R15") (pin "1") (pinfunction "1_1") (pintype "passive"))
      (node (ref "T3") (pin "2") (pinfunction "2_2") (pintype "bidirectional"))
      (node (ref "U2") (pin "24") (pinfunction "RTS_24") (pintype "output"))
    )
    (net (code "67") (name "SD0") (class "Default")
      (node (ref "ESP32_WROOM32D") (pin "21_SD0") (pinfunction "21_SD0_21_SD0") (pintype "bidirectional"))
      (node (ref "PIN_R") (pin "P$18") (pinfunction "P$18_P$18") (pintype "bidirectional"))
    )
    (net (code "68") (name "SD1") (class "Default")
      (node (ref "ESP32_WROOM32D") (pin "22_SD1") (pinfunction "22_SD1_22_SD1") (pintype "bidirectional"))
      (node (ref "PIN_R") (pin "P$17") (pinfunction "P$17_P$17") (pintype "bidirectional"))
    )
    (net (code "69") (name "SD2") (class "Default")
      (node (ref "ESP32_WROOM32D") (pin "17_SD2") (pinfunction "17_SD2_17_SD2") (pintype "bidirectional"))
      (node (ref "PIN_L") (pin "P$16") (pinfunction "P$16_P$16") (pintype "bidirectional"))
    )
    (net (code "70") (name "SD3") (class "Default")
      (node (ref "ESP32_WROOM32D") (pin "18_SD3") (pinfunction "18_SD3_18_SD3") (pintype "bidirectional"))
      (node (ref "PIN_L") (pin "P$17") (pinfunction "P$17_P$17") (pintype "bidirectional"))
    )
    (net (code "71") (name "SENSOR_VP") (class "Default")
      (node (ref "ESP32_WROOM32D") (pin "4_SENSOR_VP") (pinfunction "4_SENSOR_VP_4_SENSOR_VP") (pintype "bidirectional"))
      (node (ref "PIN_L") (pin "P$3") (pinfunction "P$3_P$3") (pintype "bidirectional"))
    )
    (net (code "72") (name "SERVO1") (class "Default")
      (node (ref "CON2") (pin "3") (pinfunction "3_3") (pintype "bidirectional"))
      (node (ref "ESP32_WROOM32D") (pin "8_IO32") (pinfunction "8_IO32_8_IO32") (pintype "bidirectional"))
      (node (ref "PIN_L") (pin "P$7") (pinfunction "P$7_P$7") (pintype "bidirectional"))
    )
    (net (code "73") (name "SERVO2") (class "Default")
      (node (ref "CON3") (pin "3") (pinfunction "3_3") (pintype "bidirectional"))
      (node (ref "ESP32_WROOM32D") (pin "9_IO33") (pinfunction "9_IO33_9_IO33") (pintype "bidirectional"))
      (node (ref "PIN_L") (pin "P$8") (pinfunction "P$8_P$8") (pintype "bidirectional"))
    )
    (net (code "74") (name "unconnected-(EN1-PadA)") (class "Default")
      (node (ref "EN1") (pin "A") (pinfunction "A_A") (pintype "bidirectional"))
    )
    (net (code "75") (name "unconnected-(EN1-PadC)") (class "Default")
      (node (ref "EN1") (pin "C") (pinfunction "C_C") (pintype "bidirectional"))
    )
    (net (code "76") (name "unconnected-(GPS-1PPS-PadP5)") (class "Default")
      (node (ref "GPS") (pin "P5") (pinfunction "1PPS_P5") (pintype "bidirectional"))
    )
    (net (code "77") (name "unconnected-(IM-IO2-Pad$P2)") (class "Default")
      (node (ref "IM") (pin "$P2") (pinfunction "IO2_$P2") (pintype "bidirectional"))
    )
    (net (code "78") (name "unconnected-(IM-IO5-Pad$P5)") (class "Default")
      (node (ref "IM") (pin "$P5") (pinfunction "IO5_$P5") (pintype "bidirectional"))
    )
    (net (code "79") (name "unconnected-(IM-IO8-Pad$P8)") (class "Default")
      (node (ref "IM") (pin "$P8") (pinfunction "IO8_$P8") (pintype "bidirectional"))
    )
    (net (code "80") (name "unconnected-(IM-MODE1{slash}IO9-Pad$P9)") (class "Default")
      (node (ref "IM") (pin "$P9") (pinfunction "MODE1/IO9_$P9") (pintype "bidirectional"))
    )
    (net (code "81") (name "unconnected-(IM-MODE2{slash}IO10-Pad$P10)") (class "Default")
      (node (ref "IM") (pin "$P10") (pinfunction "MODE2/IO10_$P10") (pintype "bidirectional"))
    )
    (net (code "82") (name "unconnected-(IM-REG-Pad$P16)") (class "Default")
      (node (ref "IM") (pin "$P16") (pinfunction "REG_$P16") (pintype "bidirectional"))
    )
    (net (code "83") (name "unconnected-(IM-SLEEP{slash}IO4-Pad$P4)") (class "Default")
      (node (ref "IM") (pin "$P4") (pinfunction "SLEEP/IO4_$P4") (pintype "bidirectional"))
    )
    (net (code "84") (name "unconnected-(IM-XMIT{slash}IO3-Pad$P3)") (class "Default")
      (node (ref "IM") (pin "$P3") (pinfunction "XMIT/IO3_$P3") (pintype "bidirectional"))
    )
    (net (code "85") (name "unconnected-(IO1-PadA)") (class "Default")
      (node (ref "IO1") (pin "A") (pinfunction "A_A") (pintype "bidirectional"))
    )
    (net (code "86") (name "unconnected-(IO1-PadC)") (class "Default")
      (node (ref "IO1") (pin "C") (pinfunction "C_C") (pintype "bidirectional"))
    )
    (net (code "87") (name "unconnected-(RASPBERRYPI_4B-Pad3V3_1)") (class "Default")
      (node (ref "RASPBERRYPI_4B") (pin "3V3_1") (pinfunction "3V3_1_3V3_1") (pintype "bidirectional"))
    )
    (net (code "88") (name "unconnected-(RASPBERRYPI_4B-Pad3V3_2)") (class "Default")
      (node (ref "RASPBERRYPI_4B") (pin "3V3_2") (pinfunction "3V3_2_3V3_2") (pintype "bidirectional"))
    )
    (net (code "89") (name "unconnected-(RASPBERRYPI_4B-Pad5V_2)") (class "Default")
      (node (ref "RASPBERRYPI_4B") (pin "5V_2") (pinfunction "5V_2_5V_2") (pintype "bidirectional"))
    )
    (net (code "90") (name "unconnected-(RASPBERRYPI_4B-PadGPIO4)") (class "Default")
      (node (ref "RASPBERRYPI_4B") (pin "GPIO4") (pinfunction "GPIO4_GPIO4") (pintype "bidirectional"))
    )
    (net (code "91") (name "unconnected-(RASPBERRYPI_4B-PadGPIO5)") (class "Default")
      (node (ref "RASPBERRYPI_4B") (pin "GPIO5") (pinfunction "GPIO5_GPIO5") (pintype "bidirectional"))
    )
    (net (code "92") (name "unconnected-(RASPBERRYPI_4B-PadGPIO6)") (class "Default")
      (node (ref "RASPBERRYPI_4B") (pin "GPIO6") (pinfunction "GPIO6_GPIO6") (pintype "bidirectional"))
    )
    (net (code "93") (name "unconnected-(RASPBERRYPI_4B-PadGPIO7)") (class "Default")
      (node (ref "RASPBERRYPI_4B") (pin "GPIO7") (pinfunction "GPIO7_GPIO7") (pintype "bidirectional"))
    )
    (net (code "94") (name "unconnected-(RASPBERRYPI_4B-PadGPIO12)") (class "Default")
      (node (ref "RASPBERRYPI_4B") (pin "GPIO12") (pinfunction "GPIO12_GPIO12") (pintype "bidirectional"))
    )
    (net (code "95") (name "unconnected-(RASPBERRYPI_4B-PadGPIO13)") (class "Default")
      (node (ref "RASPBERRYPI_4B") (pin "GPIO13") (pinfunction "GPIO13_GPIO13") (pintype "bidirectional"))
    )
    (net (code "96") (name "unconnected-(RASPBERRYPI_4B-PadGPIO16)") (class "Default")
      (node (ref "RASPBERRYPI_4B") (pin "GPIO16") (pinfunction "GPIO16_GPIO16") (pintype "bidirectional"))
    )
    (net (code "97") (name "unconnected-(RASPBERRYPI_4B-PadGPIO18)") (class "Default")
      (node (ref "RASPBERRYPI_4B") (pin "GPIO18") (pinfunction "GPIO18_GPIO18") (pintype "bidirectional"))
    )
    (net (code "98") (name "unconnected-(RASPBERRYPI_4B-PadGPIO19)") (class "Default")
      (node (ref "RASPBERRYPI_4B") (pin "GPIO19") (pinfunction "GPIO19_GPIO19") (pintype "bidirectional"))
    )
    (net (code "99") (name "unconnected-(RASPBERRYPI_4B-PadGPIO20)") (class "Default")
      (node (ref "RASPBERRYPI_4B") (pin "GPIO20") (pinfunction "GPIO20_GPIO20") (pintype "bidirectional"))
    )
    (net (code "100") (name "unconnected-(RASPBERRYPI_4B-PadGPIO21)") (class "Default")
      (node (ref "RASPBERRYPI_4B") (pin "GPIO21") (pinfunction "GPIO21_GPIO21") (pintype "bidirectional"))
    )
    (net (code "101") (name "unconnected-(RASPBERRYPI_4B-PadGPIO23)") (class "Default")
      (node (ref "RASPBERRYPI_4B") (pin "GPIO23") (pinfunction "GPIO23_GPIO23") (pintype "bidirectional"))
    )
    (net (code "102") (name "unconnected-(RASPBERRYPI_4B-PadGPIO24)") (class "Default")
      (node (ref "RASPBERRYPI_4B") (pin "GPIO24") (pinfunction "GPIO24_GPIO24") (pintype "bidirectional"))
    )
    (net (code "103") (name "unconnected-(RASPBERRYPI_4B-PadGPIO25)") (class "Default")
      (node (ref "RASPBERRYPI_4B") (pin "GPIO25") (pinfunction "GPIO25_GPIO25") (pintype "bidirectional"))
    )
    (net (code "104") (name "unconnected-(RASPBERRYPI_4B-PadGPIO26)") (class "Default")
      (node (ref "RASPBERRYPI_4B") (pin "GPIO26") (pinfunction "GPIO26_GPIO26") (pintype "bidirectional"))
    )
    (net (code "105") (name "unconnected-(SW1-PadR)") (class "Default")
      (node (ref "SW1") (pin "R") (pinfunction "R_R") (pintype "bidirectional"))
    )
    (net (code "106") (name "unconnected-(U2-CHR0-Pad15)") (class "Default")
      (node (ref "U2") (pin "15") (pinfunction "CHR0_15") (pintype "output"))
    )
    (net (code "107") (name "unconnected-(U2-CHR1-Pad14)") (class "Default")
      (node (ref "U2") (pin "14") (pinfunction "CHR1_14") (pintype "output"))
    )
    (net (code "108") (name "unconnected-(U2-CHREN-Pad13)") (class "Default")
      (node (ref "U2") (pin "13") (pinfunction "CHREN_13") (pintype "output"))
    )
    (net (code "109") (name "unconnected-(U2-CTS-Pad23)") (class "Default")
      (node (ref "U2") (pin "23") (pinfunction "CTS_23") (pintype "input"))
    )
    (net (code "110") (name "unconnected-(U2-DCD-Pad1)") (class "Default")
      (node (ref "U2") (pin "1") (pinfunction "DCD_1") (pintype "input"))
    )
    (net (code "111") (name "unconnected-(U2-DSR-Pad27)") (class "Default")
      (node (ref "U2") (pin "27") (pinfunction "DSR_27") (pintype "input"))
    )
    (net (code "112") (name "unconnected-(U2-GPIO.0{slash}TXT-Pad19)") (class "Default")
      (node (ref "U2") (pin "19") (pinfunction "GPIO.0/TXT_19") (pintype "bidirectional"))
    )
    (net (code "113") (name "unconnected-(U2-GPIO.1{slash}RXT-Pad18)") (class "Default")
      (node (ref "U2") (pin "18") (pinfunction "GPIO.1/RXT_18") (pintype "bidirectional"))
    )
    (net (code "114") (name "unconnected-(U2-GPIO.2{slash}RS485-Pad17)") (class "Default")
      (node (ref "U2") (pin "17") (pinfunction "GPIO.2/RS485_17") (pintype "bidirectional"))
    )
    (net (code "115") (name "unconnected-(U2-GPIO.3{slash}WAKEUP-Pad16)") (class "Default")
      (node (ref "U2") (pin "16") (pinfunction "GPIO.3/WAKEUP_16") (pintype "bidirectional"))
    )
    (net (code "116") (name "unconnected-(U2-GPIO.4-Pad22)") (class "Default")
      (node (ref "U2") (pin "22") (pinfunction "GPIO.4_22") (pintype "bidirectional"))
    )
    (net (code "117") (name "unconnected-(U2-GPIO.5-Pad21)") (class "Default")
      (node (ref "U2") (pin "21") (pinfunction "GPIO.5_21") (pintype "bidirectional"))
    )
    (net (code "118") (name "unconnected-(U2-GPIO.6-Pad20)") (class "Default")
      (node (ref "U2") (pin "20") (pinfunction "GPIO.6_20") (pintype "bidirectional"))
    )
    (net (code "119") (name "unconnected-(U2-NC-Pad10)") (class "Default")
      (node (ref "U2") (pin "10") (pinfunction "NC_10") (pintype "no_connect"))
    )
    (net (code "120") (name "unconnected-(U2-RI{slash}CLK-Pad2)") (class "Default")
      (node (ref "U2") (pin "2") (pinfunction "RI/CLK_2") (pintype "bidirectional"))
    )
    (net (code "121") (name "unconnected-(U2-SUSPEND-Pad12)") (class "Default")
      (node (ref "U2") (pin "12") (pinfunction "SUSPEND_12") (pintype "output"))
    )
    (net (code "122") (name "unconnected-(USB2-4_ID-Pad4)") (class "Default")
      (node (ref "USB2") (pin "4") (pinfunction "4_ID_4") (pintype "bidirectional"))
    )
  )
)
